# lvc-delay-line.net
KiCad netlist of a schematic drawn in EAGLE
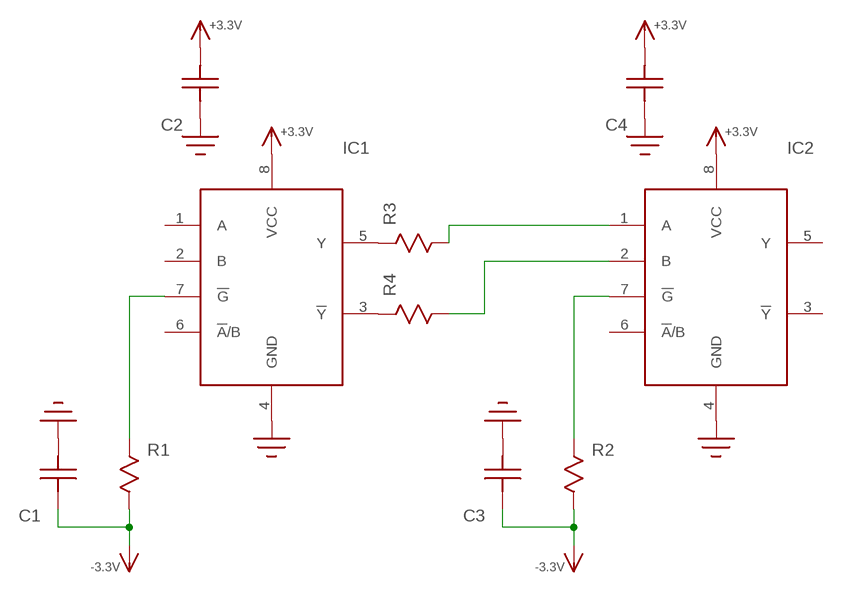
[diagram p0: schematic, sheet 1]

(export (version "E")
  (design (tool "Eeschema 10.0.6"))
  (components
    (comp (ref "C1")
      (value "C0603")
      (footprint "eagle-import:C0603")
      (libsource (lib "eagle-import") (part "C0603"))
    )
    (comp (ref "C2")
      (value "C0603")
      (footprint "eagle-import:C0603")
      (libsource (lib "eagle-import") (part "C0603"))
    )
    (comp (ref "C3")
      (value "C0603")
      (footprint "eagle-import:C0603")
      (libsource (lib "eagle-import") (part "C0603"))
    )
    (comp (ref "C4")
      (value "C0603")
      (footprint "eagle-import:C0603")
      (libsource (lib "eagle-import") (part "C0603"))
    )
    (comp (ref "IC1")
      (value "74LVC2G157")
      (footprint "eagle-import:SSOP8")
      (libsource (lib "eagle-import") (part "74LVC2G157"))
    )
    (comp (ref "IC2")
      (value "74LVC2G157")
      (footprint "eagle-import:SSOP8")
      (libsource (lib "eagle-import") (part "74LVC2G157"))
    )
    (comp (ref "R1")
      (value "R0603")
      (footprint "eagle-import:R0603")
      (libsource (lib "eagle-import") (part "R0603"))
    )
    (comp (ref "R2")
      (value "R0603")
      (footprint "eagle-import:R0603")
      (libsource (lib "eagle-import") (part "R0603"))
    )
    (comp (ref "R3")
      (value "R0402")
      (footprint "eagle-import:0402")
      (libsource (lib "eagle-import") (part "R0402"))
    )
    (comp (ref "R4")
      (value "R0402")
      (footprint "eagle-import:0402")
      (libsource (lib "eagle-import") (part "R0402"))
    )
  )
  (nets
    (net (code "1") (name "+3.3V") (class "Default")
      (node (ref "C2") (pin "P$1") (pinfunction "P$1_P$1") (pintype "bidirectional"))
      (node (ref "C4") (pin "P$1") (pinfunction "P$1_P$1") (pintype "bidirectional"))
      (node (ref "IC1") (pin "8") (pinfunction "VCC_8") (pintype "bidirectional"))
      (node (ref "IC2") (pin "8") (pinfunction "VCC_8") (pintype "bidirectional"))
    )
    (net (code "2") (name "-3.3V") (class "Default")
      (node (ref "C1") (pin "P$2") (pinfunction "P$2_P$2") (pintype "bidirectional"))
      (node (ref "C3") (pin "P$2") (pinfunction "P$2_P$2") (pintype "bidirectional"))
      (node (ref "R1") (pin "P$2") (pinfunction "P$4_P$2") (pintype "bidirectional"))
      (node (ref "R2") (pin "P$2") (pinfunction "P$4_P$2") (pintype "bidirectional"))
    )
    (net (code "3") (name "GND") (class "Default")
      (node (ref "C1") (pin "P$1") (pinfunction "P$1_P$1") (pintype "bidirectional"))
      (node (ref "C2") (pin "P$2") (pinfunction "P$2_P$2") (pintype "bidirectional"))
      (node (ref "C3") (pin "P$1") (pinfunction "P$1_P$1") (pintype "bidirectional"))
      (node (ref "C4") (pin "P$2") (pinfunction "P$2_P$2") (pintype "bidirectional"))
      (node (ref "IC1") (pin "4") (pinfunction "GND_4") (pintype "bidirectional"))
      (node (ref "IC2") (pin "4") (pinfunction "GND_4") (pintype "bidirectional"))
    )
    (net (code "4") (name "Net-(IC1-Y)") (class "Default")
      (node (ref "IC1") (pin "5") (pinfunction "Y_5") (pintype "bidirectional"))
      (node (ref "R3") (pin "1") (pinfunction "P$3_1") (pintype "bidirectional"))
    )
    (net (code "5") (name "Net-(IC1-~{G})") (class "Default")
      (node (ref "IC1") (pin "7") (pinfunction "~{G}_7") (pintype "bidirectional"))
      (node (ref "R1") (pin "P$1") (pinfunction "P$3_P$1") (pintype "bidirectional"))
    )
    (net (code "6") (name "Net-(IC1-~{Y})") (class "Default")
      (node (ref "IC1") (pin "3") (pinfunction "~{Y}_3") (pintype "bidirectional"))
      (node (ref "R4") (pin "1") (pinfunction "P$3_1") (pintype "bidirectional"))
    )
    (net (code "7") (name "Net-(IC2-A)") (class "Default")
      (node (ref "IC2") (pin "1") (pinfunction "A_1") (pintype "bidirectional"))
      (node (ref "R3") (pin "2") (pinfunction "P$4_2") (pintype "bidirectional"))
    )
    (net (code "8") (name "Net-(IC2-B)") (class "Default")
      (node (ref "IC2") (pin "2") (pinfunction "B_2") (pintype "bidirectional"))
      (node (ref "R4") (pin "2") (pinfunction "P$4_2") (pintype "bidirectional"))
    )
    (net (code "9") (name "Net-(IC2-~{G})") (class "Default")
      (node (ref "IC2") (pin "7") (pinfunction "~{G}_7") (pintype "bidirectional"))
      (node (ref "R2") (pin "P$1") (pinfunction "P$3_P$1") (pintype "bidirectional"))
    )
    (net (code "10") (name "unconnected-(IC1-A-Pad1)") (class "Default")
      (node (ref "IC1") (pin "1") (pinfunction "A_1") (pintype "bidirectional"))
    )
    (net (code "11") (name "unconnected-(IC1-B-Pad2)") (class "Default")
      (node (ref "IC1") (pin "2") (pinfunction "B_2") (pintype "bidirectional"))
    )
    (net (code "12") (name "unconnected-(IC1-~{A}{slash}B-Pad6)") (class "Default")
      (node (ref "IC1") (pin "6") (pinfunction "~{A}/B_6") (pintype "bidirectional"))
    )
    (net (code "13") (name "unconnected-(IC2-Y-Pad5)") (class "Default")
      (node (ref "IC2") (pin "5") (pinfunction "Y_5") (pintype "bidirectional"))
    )
    (net (code "14") (name "unconnected-(IC2-~{A}{slash}B-Pad6)") (class "Default")
      (node (ref "IC2") (pin "6") (pinfunction "~{A}/B_6") (pintype "bidirectional"))
    )
    (net (code "15") (name "unconnected-(IC2-~{Y}-Pad3)") (class "Default")
      (node (ref "IC2") (pin "3") (pinfunction "~{Y}_3") (pintype "bidirectional"))
    )
  )
)
